# digAudio-rcj-da101jc.net
KiCad netlist of a schematic drawn in EAGLE
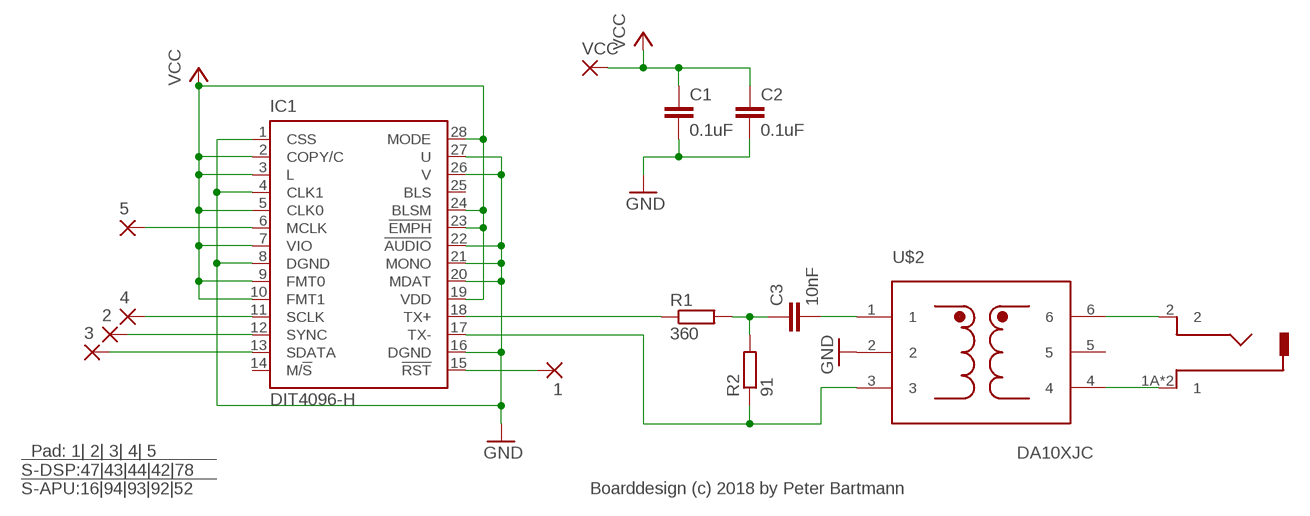
[diagram p0: schematic, sheet 1]

(export (version "E")
  (design (tool "Eeschema 10.0.6"))
  (components
    (comp (ref "1")
      (value "SMD1")
      (footprint "eagle-import:SMD0,8-1,6")
      (libsource (lib "eagle-import") (part "SMD1"))
    )
    (comp (ref "2")
      (value "SMD1")
      (footprint "eagle-import:SMD0,8-1,6")
      (libsource (lib "eagle-import") (part "SMD1"))
    )
    (comp (ref "3")
      (value "SMD1")
      (footprint "eagle-import:SMD0,8-1,6")
      (libsource (lib "eagle-import") (part "SMD1"))
    )
    (comp (ref "4")
      (value "SMD1")
      (footprint "eagle-import:SMD0,8-1,6")
      (libsource (lib "eagle-import") (part "SMD1"))
    )
    (comp (ref "5")
      (value "SMD1")
      (footprint "eagle-import:SMD0,8-1,6")
      (libsource (lib "eagle-import") (part "SMD1"))
    )
    (comp (ref "C1")
      (value "0.1uF")
      (footprint "eagle-import:C0603")
      (libsource (lib "eagle-import") (part "C-EUC0603"))
    )
    (comp (ref "C2")
      (value "0.1uF")
      (footprint "eagle-import:C0603")
      (libsource (lib "eagle-import") (part "C-EUC0603"))
    )
    (comp (ref "C3")
      (value "10nF")
      (footprint "eagle-import:C0603")
      (libsource (lib "eagle-import") (part "C-EUC0603"))
    )
    (comp (ref "IC1")
      (value "DIT4096-H")
      (footprint "eagle-import:PW_R-PDSO-G28")
      (fields (field (name "MF") "TEXAS INSTRUMENTS") (field (name "MPN") "DIT4192IPW"))
      (libsource (lib "eagle-import") (part "DIT4192-H"))
    )
    (comp (ref "R1")
      (value "360")
      (footprint "eagle-import:R0603")
      (libsource (lib "eagle-import") (part "R-EU_R0603"))
    )
    (comp (ref "R2")
      (value "91")
      (footprint "eagle-import:R0603")
      (libsource (lib "eagle-import") (part "R-EU_R0603"))
    )
    (comp (ref "U$1")
      (value "RCJ-013-SMT-TR")
      (footprint "eagle-import:RCJ_01X_SMT_MODIFIED")
      (libsource (lib "eagle-import") (part "RCJ_01X_SMT-MODIFIED"))
    )
    (comp (ref "U$2")
      (value "DA10XJC")
      (footprint "eagle-import:DA101JC")
      (libsource (lib "eagle-import") (part "DA10XJC"))
    )
    (comp (ref "VCC")
      (value "SMD2")
      (footprint "eagle-import:SMD1,27-2,54")
      (libsource (lib "eagle-import") (part "SMD2"))
    )
  )
  (nets
    (net (code "1") (name "GND") (class "Default")
      (node (ref "C1") (pin "2") (pinfunction "2_2") (pintype "passive"))
      (node (ref "C2") (pin "2") (pinfunction "2_2") (pintype "passive"))
      (node (ref "IC1") (pin "1") (pinfunction "CSS_1") (pintype "input"))
      (node (ref "IC1") (pin "16") (pinfunction "DGND_16") (pintype "power_in"))
      (node (ref "IC1") (pin "20") (pinfunction "MDAT_20") (pintype "input"))
      (node (ref "IC1") (pin "21") (pinfunction "MONO_21") (pintype "input"))
      (node (ref "IC1") (pin "22") (pinfunction "~{AUDIO}_22") (pintype "input"))
      (node (ref "IC1") (pin "26") (pinfunction "V_26") (pintype "input"))
      (node (ref "IC1") (pin "27") (pinfunction "U_27") (pintype "input"))
      (node (ref "IC1") (pin "4") (pinfunction "CLK1_4") (pintype "input"))
      (node (ref "IC1") (pin "8") (pinfunction "DGND_8") (pintype "power_in"))
      (node (ref "U$2") (pin "2") (pinfunction "2_2") (pintype "bidirectional"))
    )
    (net (code "2") (name "Net-(1-P)") (class "Default")
      (node (ref "1") (pin "P$1") (pinfunction "P_P$1") (pintype "passive"))
      (node (ref "IC1") (pin "15") (pinfunction "~{RST}_15") (pintype "input"))
    )
    (net (code "3") (name "Net-(2-P)") (class "Default")
      (node (ref "2") (pin "P$1") (pinfunction "P_P$1") (pintype "passive"))
      (node (ref "IC1") (pin "12") (pinfunction "SYNC_12") (pintype "bidirectional"))
    )
    (net (code "4") (name "Net-(3-P)") (class "Default")
      (node (ref "3") (pin "P$1") (pinfunction "P_P$1") (pintype "passive"))
      (node (ref "IC1") (pin "13") (pinfunction "SDATA_13") (pintype "input"))
    )
    (net (code "5") (name "Net-(4-P)") (class "Default")
      (node (ref "4") (pin "P$1") (pinfunction "P_P$1") (pintype "passive"))
      (node (ref "IC1") (pin "11") (pinfunction "SCLK_11") (pintype "bidirectional"))
    )
    (net (code "6") (name "Net-(5-P)") (class "Default")
      (node (ref "5") (pin "P$1") (pinfunction "P_P$1") (pintype "passive"))
      (node (ref "IC1") (pin "6") (pinfunction "MCLK_6") (pintype "input"))
    )
    (net (code "7") (name "Net-(C3-Pad1)") (class "Default")
      (node (ref "C3") (pin "1") (pinfunction "1_1") (pintype "passive"))
      (node (ref "R1") (pin "2") (pinfunction "2_2") (pintype "passive"))
      (node (ref "R2") (pin "2") (pinfunction "2_2") (pintype "passive"))
    )
    (net (code "8") (name "Net-(C3-Pad2)") (class "Default")
      (node (ref "C3") (pin "2") (pinfunction "2_2") (pintype "passive"))
      (node (ref "U$2") (pin "1") (pinfunction "1_1") (pintype "bidirectional"))
    )
    (net (code "9") (name "Net-(IC1-TX+)") (class "Default")
      (node (ref "IC1") (pin "18") (pinfunction "TX+_18") (pintype "output"))
      (node (ref "R1") (pin "1") (pinfunction "1_1") (pintype "passive"))
    )
    (net (code "10") (name "Net-(IC1-TX-)") (class "Default")
      (node (ref "IC1") (pin "17") (pinfunction "TX-_17") (pintype "output"))
      (node (ref "R2") (pin "1") (pinfunction "1_1") (pintype "passive"))
      (node (ref "U$2") (pin "3") (pinfunction "3_3") (pintype "bidirectional"))
    )
    (net (code "11") (name "Net-(U$1-1-Pad1A)") (class "Default")
      (node (ref "U$1") (pin "1A") (pinfunction "1_1A") (pintype "bidirectional"))
      (node (ref "U$1") (pin "1B") (pinfunction "1_1B") (pintype "bidirectional"))
      (node (ref "U$2") (pin "4") (pinfunction "4_4") (pintype "bidirectional"))
    )
    (net (code "12") (name "Net-(U$1-Pad2)") (class "Default")
      (node (ref "U$1") (pin "2") (pinfunction "2_2") (pintype "bidirectional"))
      (node (ref "U$2") (pin "6") (pinfunction "6_6") (pintype "bidirectional"))
    )
    (net (code "13") (name "VCC") (class "Default")
      (node (ref "C1") (pin "1") (pinfunction "1_1") (pintype "passive"))
      (node (ref "C2") (pin "1") (pinfunction "1_1") (pintype "passive"))
      (node (ref "IC1") (pin "10") (pinfunction "FMT1_10") (pintype "input"))
      (node (ref "IC1") (pin "19") (pinfunction "VDD_19") (pintype "power_in"))
      (node (ref "IC1") (pin "2") (pinfunction "COPY/C_2") (pintype "input"))
      (node (ref "IC1") (pin "23") (pinfunction "~{EMPH}_23") (pintype "input"))
      (node (ref "IC1") (pin "24") (pinfunction "BLSM_24") (pintype "input"))
      (node (ref "IC1") (pin "28") (pinfunction "MODE_28") (pintype "input"))
      (node (ref "IC1") (pin "3") (pinfunction "L_3") (pintype "input"))
      (node (ref "IC1") (pin "5") (pinfunction "CLK0_5") (pintype "input"))
      (node (ref "IC1") (pin "7") (pinfunction "VIO_7") (pintype "power_in"))
      (node (ref "IC1") (pin "9") (pinfunction "FMT0_9") (pintype "input"))
      (node (ref "VCC") (pin "1") (pinfunction "P_1") (pintype "passive"))
    )
    (net (code "14") (name "unconnected-(IC1-BLS-Pad25)") (class "Default")
      (node (ref "IC1") (pin "25") (pinfunction "BLS_25") (pintype "bidirectional"))
    )
    (net (code "15") (name "unconnected-(IC1-M{slash}~{S}-Pad14)") (class "Default")
      (node (ref "IC1") (pin "14") (pinfunction "M/~{S}_14") (pintype "input"))
    )
    (net (code "16") (name "unconnected-(U$2-Pad5)") (class "Default")
      (node (ref "U$2") (pin "5") (pinfunction "5_5") (pintype "bidirectional"))
    )
  )
)
